# Ethernet_bridge_BOT.net
KiCad netlist of a schematic drawn in Altium Designer
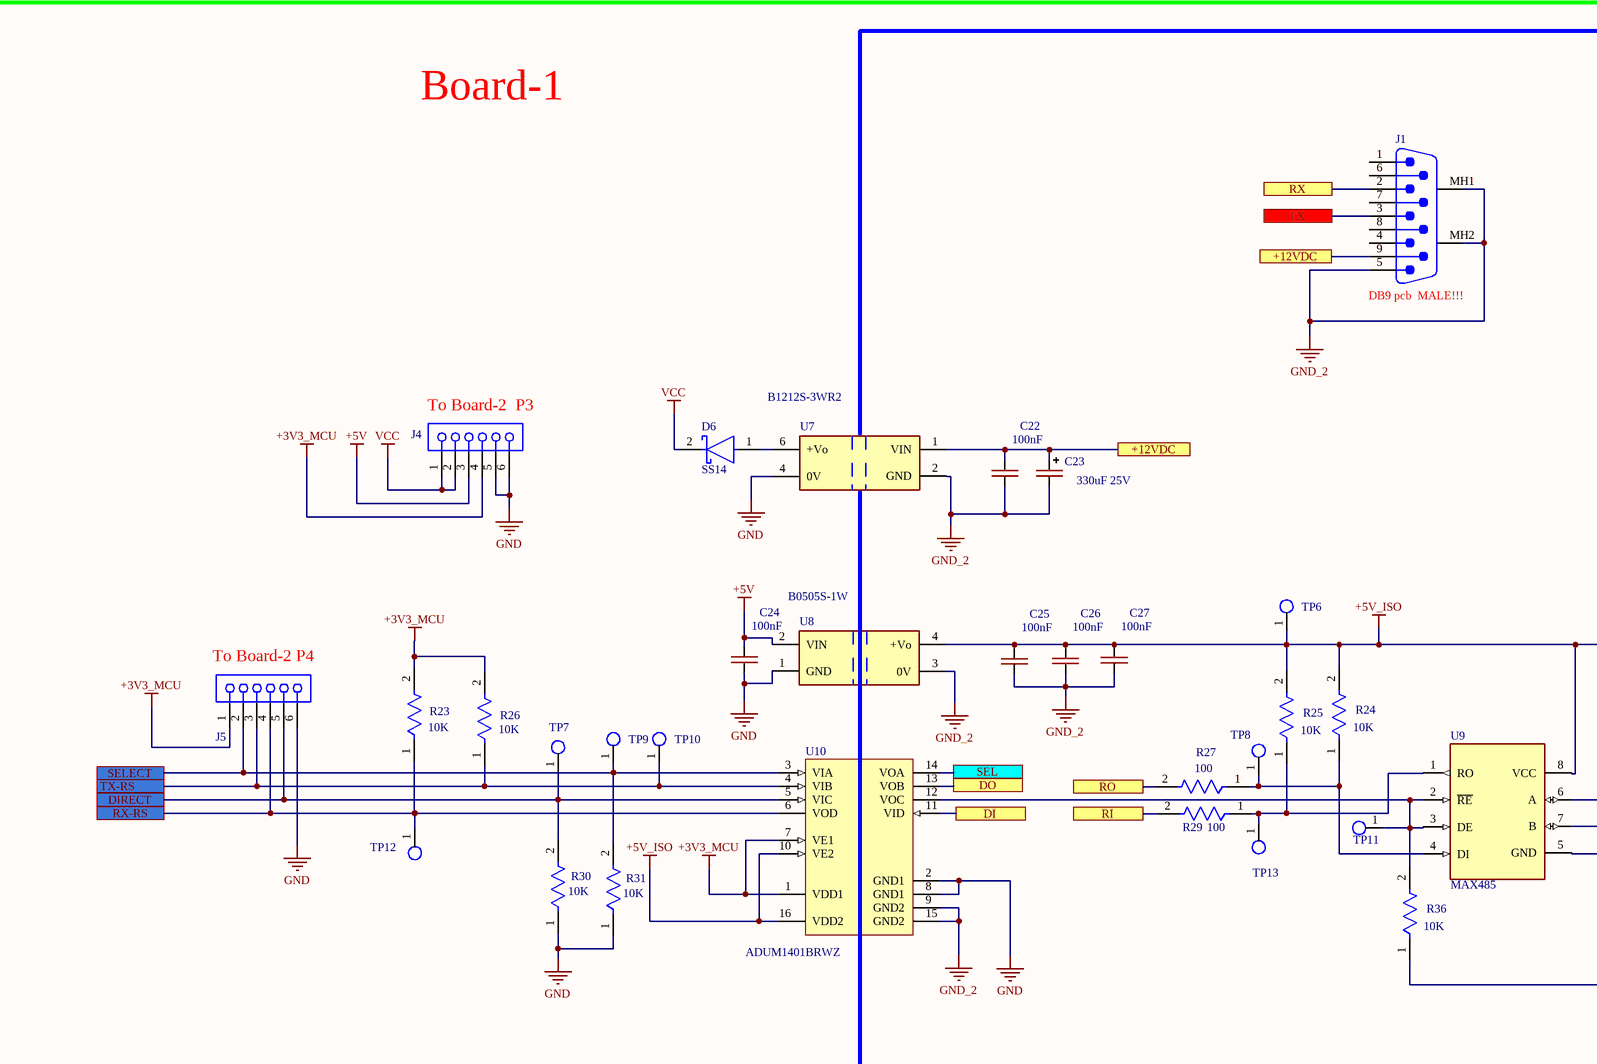
[diagram p0: Ethernet_bridge(BOT).SchDoc, left]
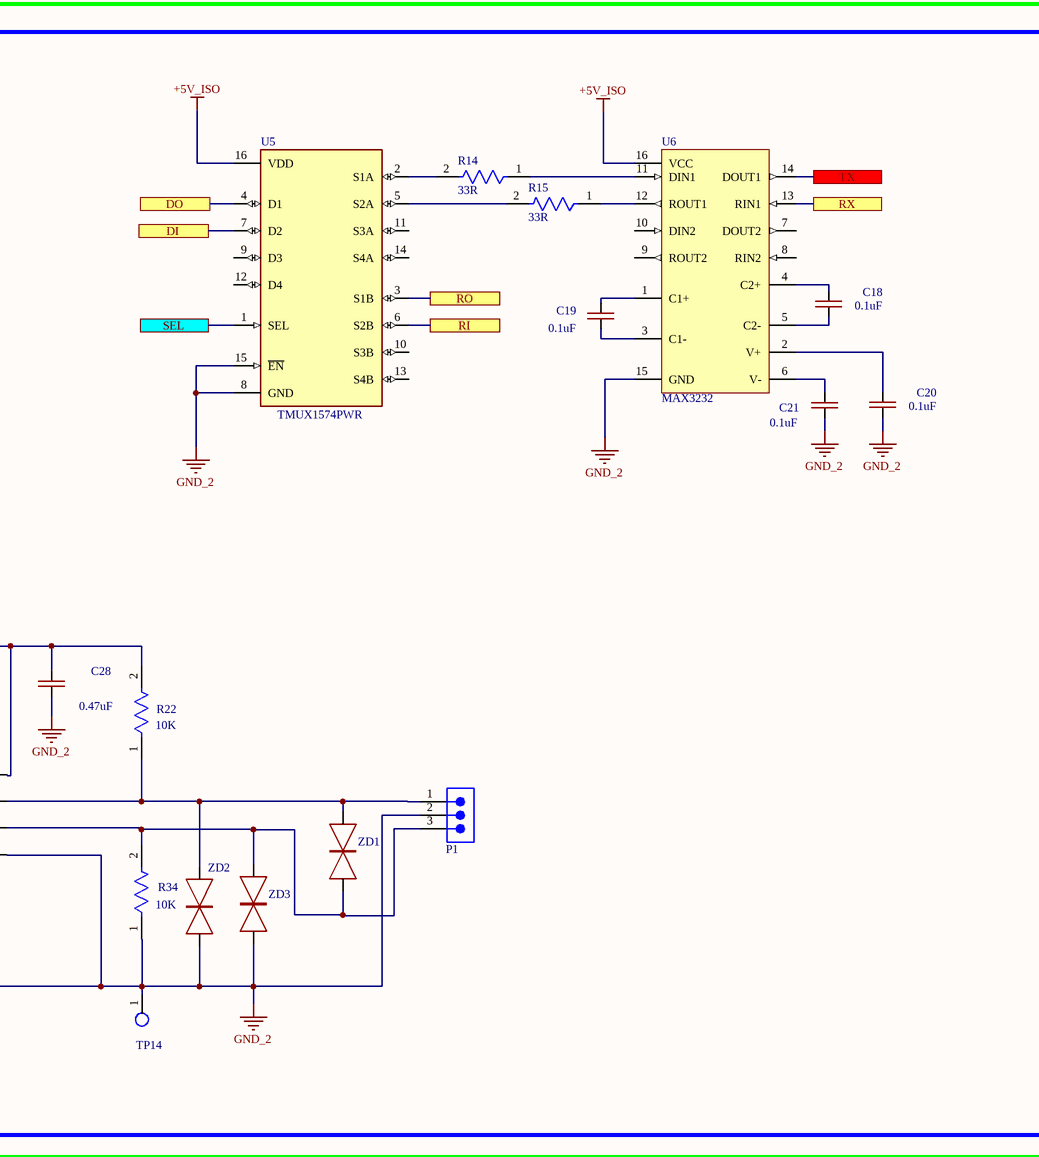
[diagram p1: Ethernet_bridge(BOT).SchDoc, right]

(export (version "E")
  (design (tool "Eeschema 10.0.6"))
  (components
    (comp (ref "C18")
      (value "0.1uF")
      (footprint "CAP-0603")
      (libsource (lib "PASSIVE_COMPONENTS") (part "CAP-NON-POLAR"))
    )
    (comp (ref "C19")
      (value "0.1uF")
      (footprint "CAP-0603")
      (libsource (lib "PASSIVE_COMPONENTS") (part "CAP-NON-POLAR"))
    )
    (comp (ref "C20")
      (value "0.1uF")
      (footprint "CAP-0603")
      (libsource (lib "PASSIVE_COMPONENTS") (part "CAP-NON-POLAR"))
    )
    (comp (ref "C21")
      (value "0.1uF")
      (footprint "CAP-0603")
      (libsource (lib "PASSIVE_COMPONENTS") (part "CAP-NON-POLAR"))
    )
    (comp (ref "C22")
      (value "100nF")
      (footprint "CAP-0603")
      (libsource (lib "PASSIVE_COMPONENTS") (part "CAP-NON-POLAR"))
    )
    (comp (ref "C23")
      (value "330uF 25V")
      (footprint "CAP_SMD_Size_E")
      (libsource (lib "PASSIVE_COMPONENTS") (part "CAP_POL_SMD"))
    )
    (comp (ref "C24")
      (value "100nF")
      (footprint "CAP-0603")
      (libsource (lib "PASSIVE_COMPONENTS") (part "CAP-NON-POLAR"))
    )
    (comp (ref "C25")
      (value "100nF")
      (footprint "CAP-0603")
      (libsource (lib "PASSIVE_COMPONENTS") (part "CAP-NON-POLAR"))
    )
    (comp (ref "C26")
      (value "100nF")
      (footprint "CAP-0603")
      (libsource (lib "PASSIVE_COMPONENTS") (part "CAP-NON-POLAR"))
    )
    (comp (ref "C27")
      (value "100nF")
      (footprint "CAP-0603")
      (libsource (lib "PASSIVE_COMPONENTS") (part "CAP-NON-POLAR"))
    )
    (comp (ref "C28")
      (value "0.47uF")
      (footprint "CAP-0805")
      (libsource (lib "PASSIVE_COMPONENTS") (part "CAP-NON-POLAR"))
    )
    (comp (ref "D6") (value "SS14") (footprint "DO-214-AC") (libsource (lib "Diodes") (part "SS14")))
    (comp (ref "J1")
      (value "DB9 pcb  MALE!!!")
      (footprint "DB-9_2")
      (libsource (lib "Connectors") (part "DB9"))
    )
    (comp (ref "J4")
      (value "61300611821")
      (footprint "61300611821")
      (description "WR-PHD Socket Header, THT, Vertical, pitch 2.54mm, 1 Row, 6P")
      (fields (field (name "MANUFACTURER") "Wurth Elektronik"))
      (libsource (lib "Altium_WR-PHD (rev22b)") (part "61300611821"))
    )
    (comp (ref "J5")
      (value "61300611821")
      (footprint "61300611821")
      (description "WR-PHD Socket Header, THT, Vertical, pitch 2.54mm, 1 Row, 6P")
      (fields (field (name "MANUFACTURER") "Wurth Elektronik"))
      (libsource (lib "Altium_WR-PHD (rev22b)") (part "61300611821"))
    )
    (comp (ref "P1")
      (value "691305340003")
      (footprint "691305340003")
      (description "WR-TBL Series 3053 Horizontal PCB Header, THT, pitch 3.81mm, 3p")
      (fields (field (name "MANUFACTURER") "Wurth Elektronik"))
      (libsource (lib "Altium_WR-TBL (rev23f)") (part "691305340003"))
    )
    (comp (ref "R14")
      (value "33R")
      (footprint "RES-0603")
      (libsource (lib "PASSIVE_COMPONENTS") (part "RES-CONST"))
    )
    (comp (ref "R15")
      (value "33R")
      (footprint "RES-0603")
      (libsource (lib "PASSIVE_COMPONENTS") (part "RES-CONST"))
    )
    (comp (ref "R22")
      (value "10K")
      (footprint "RES-0603")
      (libsource (lib "PASSIVE_COMPONENTS") (part "RES-CONST"))
    )
    (comp (ref "R23")
      (value "10K")
      (footprint "RES-0603")
      (libsource (lib "PASSIVE_COMPONENTS") (part "RES-CONST"))
    )
    (comp (ref "R24")
      (value "10K")
      (footprint "RES-0603")
      (libsource (lib "PASSIVE_COMPONENTS") (part "RES-CONST"))
    )
    (comp (ref "R25")
      (value "10K")
      (footprint "RES-0603")
      (libsource (lib "PASSIVE_COMPONENTS") (part "RES-CONST"))
    )
    (comp (ref "R26")
      (value "10K")
      (footprint "RES-0603")
      (libsource (lib "PASSIVE_COMPONENTS") (part "RES-CONST"))
    )
    (comp (ref "R27")
      (value "100")
      (footprint "RES-0603")
      (libsource (lib "PASSIVE_COMPONENTS") (part "RES-CONST"))
    )
    (comp (ref "R29")
      (value "100")
      (footprint "RES-0603")
      (libsource (lib "PASSIVE_COMPONENTS") (part "RES-CONST"))
    )
    (comp (ref "R30")
      (value "10K")
      (footprint "RES-0603")
      (libsource (lib "PASSIVE_COMPONENTS") (part "RES-CONST"))
    )
    (comp (ref "R31")
      (value "10K")
      (footprint "RES-0603")
      (libsource (lib "PASSIVE_COMPONENTS") (part "RES-CONST"))
    )
    (comp (ref "R34")
      (value "10K")
      (footprint "RES-0603")
      (libsource (lib "PASSIVE_COMPONENTS") (part "RES-CONST"))
    )
    (comp (ref "R36")
      (value "10K")
      (footprint "RES-0603")
      (libsource (lib "PASSIVE_COMPONENTS") (part "RES-CONST"))
    )
    (comp (ref "TP6")
      (value "Test_Point_PCB")
      (footprint "Test_Point")
      (description "Test_Point")
      (libsource (lib "Test_Point") (part "TP_PCB?"))
    )
    (comp (ref "TP7")
      (value "Test_Point_PCB")
      (footprint "Test_Point")
      (description "Test_Point")
      (libsource (lib "Test_Point") (part "TP_PCB?"))
    )
    (comp (ref "TP8")
      (value "Test_Point_PCB")
      (footprint "Test_Point")
      (description "Test_Point")
      (libsource (lib "Test_Point") (part "TP_PCB?"))
    )
    (comp (ref "TP9")
      (value "Test_Point_PCB")
      (footprint "Test_Point")
      (description "Test_Point")
      (libsource (lib "Test_Point") (part "TP_PCB?"))
    )
    (comp (ref "TP10")
      (value "Test_Point_PCB")
      (footprint "Test_Point")
      (description "Test_Point")
      (libsource (lib "Test_Point") (part "TP_PCB?"))
    )
    (comp (ref "TP11")
      (value "Test_Point_PCB")
      (footprint "Test_Point")
      (description "Test_Point")
      (libsource (lib "Test_Point") (part "TP_PCB?"))
    )
    (comp (ref "TP12")
      (value "Test_Point_PCB")
      (footprint "Test_Point")
      (description "Test_Point")
      (libsource (lib "Test_Point") (part "TP_PCB?"))
    )
    (comp (ref "TP13")
      (value "~")
      (footprint "Test_Point")
      (description "Test_Point")
      (libsource (lib "Connectors") (part "TP_PCB?"))
    )
    (comp (ref "TP14")
      (value "Test_Point_PCB")
      (footprint "Test_Point")
      (description "Test_Point")
      (libsource (lib "Test_Point") (part "TP_PCB?"))
    )
    (comp (ref "U5")
      (value "TMUX1574PWR")
      (footprint "TSSOP-16-A")
      (libsource (lib "Integrated_Circuts") (part "TMUX1574PWR"))
    )
    (comp (ref "U6")
      (value "MAX3232")
      (footprint "SOIC-16-M")
      (libsource (lib "Integrated_Circuts") (part "MAX3232"))
    )
    (comp (ref "U7")
      (value "B1212S-3WR2")
      (footprint "B1212S-3WR2")
      (libsource (lib "Integrated_Circuts") (part "B1212S-3WR2"))
    )
    (comp (ref "U8")
      (value "B0505S-1W")
      (footprint "B0505S-1W")
      (libsource (lib "Integrated_Circuts") (part "B0505S-1W"))
    )
    (comp (ref "U9")
      (value "MAX485")
      (footprint "SOIC-8-MFG")
      (libsource (lib "Integrated_Circuts") (part "MAX485"))
    )
    (comp (ref "U10")
      (value "ADUM1401BRWZ")
      (footprint "ADI-RW-16_M")
      (fields (field (name "MANUFACTURER") "Analog Devices"))
      (libsource (lib "Altium Content Vault") (part "ADI-ADUMX4X1-16"))
    )
    (comp (ref "ZD1")
      (value "P6SMB16CA")
      (footprint "DO-214AA")
      (libsource (lib "P6SMB16CA") (part "P6SMB16CA"))
    )
    (comp (ref "ZD2")
      (value "P6SMB16CA")
      (footprint "DO-214AA")
      (libsource (lib "P6SMB16CA") (part "P6SMB16CA"))
    )
    (comp (ref "ZD3")
      (value "P6SMB16CA")
      (footprint "DO-214AA")
      (libsource (lib "P6SMB16CA") (part "P6SMB16CA"))
    )
  )
  (nets
    (net (code "1") (name "+3V3_MCU") (class "Default")
      (node (ref "J4") (pin "4") (pinfunction "4_4") (pintype "passive"))
      (node (ref "J5") (pin "1") (pinfunction "1_1") (pintype "passive"))
      (node (ref "R23") (pin "2") (pinfunction "2_2") (pintype "passive"))
      (node (ref "R26") (pin "2") (pinfunction "2_2") (pintype "passive"))
      (node (ref "U10") (pin "1") (pinfunction "VDD1_1") (pintype "power_in"))
      (node (ref "U10") (pin "7") (pinfunction "VE1_7") (pintype "input"))
    )
    (net (code "2") (name "+5V") (class "Default")
      (node (ref "C24") (pin "2") (pinfunction "2_2") (pintype "passive"))
      (node (ref "J4") (pin "3") (pinfunction "3_3") (pintype "passive"))
      (node (ref "U8") (pin "2") (pinfunction "VIN_2") (pintype "power_in"))
    )
    (net (code "3") (name "+5V_ISO") (class "Default")
      (node (ref "C25") (pin "2") (pinfunction "2_2") (pintype "passive"))
      (node (ref "C26") (pin "2") (pinfunction "2_2") (pintype "passive"))
      (node (ref "C27") (pin "2") (pinfunction "2_2") (pintype "passive"))
      (node (ref "C28") (pin "1") (pinfunction "1_1") (pintype "passive"))
      (node (ref "R22") (pin "2") (pinfunction "2_2") (pintype "passive"))
      (node (ref "R24") (pin "2") (pinfunction "2_2") (pintype "passive"))
      (node (ref "R25") (pin "2") (pinfunction "2_2") (pintype "passive"))
      (node (ref "TP6") (pin "1") (pinfunction "G9_1") (pintype "passive"))
      (node (ref "U10") (pin "10") (pinfunction "VE2_10") (pintype "input"))
      (node (ref "U10") (pin "16") (pinfunction "VDD2_16") (pintype "power_in"))
      (node (ref "U5") (pin "16") (pinfunction "VDD_16") (pintype "power_in"))
      (node (ref "U6") (pin "16") (pinfunction "VCC_16") (pintype "power_in"))
      (node (ref "U8") (pin "4") (pinfunction "+Vo_4") (pintype "power_in"))
      (node (ref "U9") (pin "8") (pinfunction "VCC_8") (pintype "power_in"))
    )
    (net (code "4") (name "/+12VDC") (class "Default")
      (node (ref "C22") (pin "2") (pinfunction "2_2") (pintype "passive"))
      (node (ref "C23") (pin "1") (pinfunction "+_1") (pintype "passive"))
      (node (ref "J1") (pin "9") (pinfunction "9_9") (pintype "passive"))
      (node (ref "U7") (pin "1") (pinfunction "VIN_1") (pintype "power_in"))
    )
    (net (code "5") (name "/DI") (class "Default")
      (node (ref "U10") (pin "11") (pinfunction "VID_11") (pintype "input"))
      (node (ref "U5") (pin "7") (pinfunction "D2_7") (pintype "bidirectional"))
    )
    (net (code "6") (name "/DIRECT") (class "Default")
      (node (ref "J5") (pin "5") (pinfunction "5_5") (pintype "passive"))
      (node (ref "R30") (pin "2") (pinfunction "2_2") (pintype "passive"))
      (node (ref "TP7") (pin "1") (pinfunction "G9_1") (pintype "passive"))
      (node (ref "U10") (pin "5") (pinfunction "VIC_5") (pintype "input"))
    )
    (net (code "7") (name "/DO") (class "Default")
      (node (ref "U10") (pin "13") (pinfunction "VOB_13") (pintype "tri_state"))
      (node (ref "U5") (pin "4") (pinfunction "D1_4") (pintype "bidirectional"))
    )
    (net (code "8") (name "/RI") (class "Default")
      (node (ref "R29") (pin "2") (pinfunction "2_2") (pintype "passive"))
      (node (ref "U5") (pin "6") (pinfunction "S2B_6") (pintype "bidirectional"))
    )
    (net (code "9") (name "/RO") (class "Default")
      (node (ref "R27") (pin "2") (pinfunction "2_2") (pintype "passive"))
      (node (ref "U5") (pin "3") (pinfunction "S1B_3") (pintype "bidirectional"))
    )
    (net (code "10") (name "/RX") (class "Default")
      (node (ref "J1") (pin "2") (pinfunction "2_2") (pintype "passive"))
      (node (ref "U6") (pin "13") (pinfunction "RIN1_13") (pintype "input"))
    )
    (net (code "11") (name "/RX-RS") (class "Default")
      (node (ref "J5") (pin "4") (pinfunction "4_4") (pintype "passive"))
      (node (ref "R23") (pin "1") (pinfunction "1_1") (pintype "passive"))
      (node (ref "TP12") (pin "1") (pinfunction "G9_1") (pintype "passive"))
      (node (ref "U10") (pin "6") (pinfunction "VOD_6") (pintype "tri_state"))
    )
    (net (code "12") (name "/SEL") (class "Default")
      (node (ref "U10") (pin "14") (pinfunction "VOA_14") (pintype "tri_state"))
      (node (ref "U5") (pin "1") (pinfunction "SEL_1") (pintype "input"))
    )
    (net (code "13") (name "/SELECT") (class "Default")
      (node (ref "J5") (pin "2") (pinfunction "2_2") (pintype "passive"))
      (node (ref "R31") (pin "2") (pinfunction "2_2") (pintype "passive"))
      (node (ref "TP9") (pin "1") (pinfunction "G9_1") (pintype "passive"))
      (node (ref "U10") (pin "3") (pinfunction "VIA_3") (pintype "input"))
    )
    (net (code "14") (name "/TX") (class "Default")
      (node (ref "J1") (pin "3") (pinfunction "3_3") (pintype "passive"))
      (node (ref "U6") (pin "14") (pinfunction "DOUT1_14") (pintype "output"))
    )
    (net (code "15") (name "/TX-RS") (class "Default")
      (node (ref "J5") (pin "3") (pinfunction "3_3") (pintype "passive"))
      (node (ref "R26") (pin "1") (pinfunction "1_1") (pintype "passive"))
      (node (ref "TP10") (pin "1") (pinfunction "G9_1") (pintype "passive"))
      (node (ref "U10") (pin "4") (pinfunction "VIB_4") (pintype "input"))
    )
    (net (code "16") (name "GND") (class "Default")
      (node (ref "C24") (pin "1") (pinfunction "1_1") (pintype "passive"))
      (node (ref "J4") (pin "5") (pinfunction "5_5") (pintype "passive"))
      (node (ref "J4") (pin "6") (pinfunction "6_6") (pintype "passive"))
      (node (ref "J5") (pin "6") (pinfunction "6_6") (pintype "passive"))
      (node (ref "R30") (pin "1") (pinfunction "1_1") (pintype "passive"))
      (node (ref "R31") (pin "1") (pinfunction "1_1") (pintype "passive"))
      (node (ref "U10") (pin "2") (pinfunction "GND1_2") (pintype "power_in"))
      (node (ref "U10") (pin "8") (pinfunction "GND1_8") (pintype "power_in"))
      (node (ref "U7") (pin "4") (pinfunction "0V_4") (pintype "power_in"))
      (node (ref "U8") (pin "1") (pinfunction "GND_1") (pintype "power_in"))
    )
    (net (code "17") (name "GND_2") (class "Default")
      (node (ref "C20") (pin "1") (pinfunction "1_1") (pintype "passive"))
      (node (ref "C21") (pin "1") (pinfunction "1_1") (pintype "passive"))
      (node (ref "C22") (pin "1") (pinfunction "1_1") (pintype "passive"))
      (node (ref "C23") (pin "2") (pinfunction "-_2") (pintype "passive"))
      (node (ref "C25") (pin "1") (pinfunction "1_1") (pintype "passive"))
      (node (ref "C26") (pin "1") (pinfunction "1_1") (pintype "passive"))
      (node (ref "C27") (pin "1") (pinfunction "1_1") (pintype "passive"))
      (node (ref "C28") (pin "2") (pinfunction "2_2") (pintype "passive"))
      (node (ref "J1") (pin "5") (pinfunction "5_5") (pintype "passive"))
      (node (ref "J1") (pin "MH1") (pinfunction "MH1_MH1") (pintype "passive"))
      (node (ref "J1") (pin "MH2") (pinfunction "MH2_MH2") (pintype "passive"))
      (node (ref "P1") (pin "2") (pinfunction "2_2") (pintype "passive"))
      (node (ref "R34") (pin "1") (pinfunction "1_1") (pintype "passive"))
      (node (ref "R36") (pin "1") (pinfunction "1_1") (pintype "passive"))
      (node (ref "TP14") (pin "1") (pinfunction "G9_1") (pintype "passive"))
      (node (ref "U10") (pin "15") (pinfunction "GND2_15") (pintype "power_in"))
      (node (ref "U10") (pin "9") (pinfunction "GND2_9") (pintype "power_in"))
      (node (ref "U5") (pin "15") (pinfunction "~{EN}_15") (pintype "input"))
      (node (ref "U5") (pin "8") (pinfunction "GND_8") (pintype "power_in"))
      (node (ref "U6") (pin "15") (pinfunction "GND_15") (pintype "power_in"))
      (node (ref "U7") (pin "2") (pinfunction "GND_2") (pintype "power_in"))
      (node (ref "U8") (pin "3") (pinfunction "0V_3") (pintype "power_in"))
      (node (ref "U9") (pin "5") (pinfunction "GND_5") (pintype "power_in"))
      (node (ref "ZD2") (pin "1") (pinfunction "A_1") (pintype "passive"))
      (node (ref "ZD3") (pin "1") (pinfunction "A_1") (pintype "passive"))
    )
    (net (code "18") (name "Net-(D6-A)") (class "Default")
      (node (ref "D6") (pin "1") (pinfunction "A_1") (pintype "passive"))
      (node (ref "U7") (pin "6") (pinfunction "+Vo_6") (pintype "power_in"))
    )
    (net (code "19") (name "Net-(TP8-G9)") (class "Default")
      (node (ref "R24") (pin "1") (pinfunction "1_1") (pintype "passive"))
      (node (ref "R27") (pin "1") (pinfunction "1_1") (pintype "passive"))
      (node (ref "TP8") (pin "1") (pinfunction "G9_1") (pintype "passive"))
      (node (ref "U9") (pin "4") (pinfunction "DI_4") (pintype "input"))
    )
    (net (code "20") (name "Net-(TP11-G9)") (class "Default")
      (node (ref "R36") (pin "2") (pinfunction "2_2") (pintype "passive"))
      (node (ref "TP11") (pin "1") (pinfunction "G9_1") (pintype "passive"))
      (node (ref "U10") (pin "12") (pinfunction "VOC_12") (pintype "tri_state"))
      (node (ref "U9") (pin "2") (pinfunction "~{RE}_2") (pintype "input"))
      (node (ref "U9") (pin "3") (pinfunction "DE_3") (pintype "input"))
    )
    (net (code "21") (name "Net-(TP13-G9)") (class "Default")
      (node (ref "R25") (pin "1") (pinfunction "1_1") (pintype "passive"))
      (node (ref "R29") (pin "1") (pinfunction "1_1") (pintype "passive"))
      (node (ref "TP13") (pin "1") (pinfunction "G9_1") (pintype "passive"))
      (node (ref "U9") (pin "1") (pinfunction "RO_1") (pintype "output"))
    )
    (net (code "22") (name "Net-(U5-S1A)") (class "Default")
      (node (ref "R14") (pin "2") (pinfunction "2_2") (pintype "passive"))
      (node (ref "U5") (pin "2") (pinfunction "S1A_2") (pintype "bidirectional"))
    )
    (net (code "23") (name "Net-(U5-S2A)") (class "Default")
      (node (ref "R15") (pin "2") (pinfunction "2_2") (pintype "passive"))
      (node (ref "U5") (pin "5") (pinfunction "S2A_5") (pintype "bidirectional"))
    )
    (net (code "24") (name "Net-(U6-C1+)") (class "Default")
      (node (ref "C19") (pin "2") (pinfunction "2_2") (pintype "passive"))
      (node (ref "U6") (pin "1") (pinfunction "C1+_1") (pintype "passive"))
    )
    (net (code "25") (name "Net-(U6-C1-)") (class "Default")
      (node (ref "C19") (pin "1") (pinfunction "1_1") (pintype "passive"))
      (node (ref "U6") (pin "3") (pinfunction "C1-_3") (pintype "passive"))
    )
    (net (code "26") (name "Net-(U6-C2+)") (class "Default")
      (node (ref "C18") (pin "2") (pinfunction "2_2") (pintype "passive"))
      (node (ref "U6") (pin "4") (pinfunction "C2+_4") (pintype "passive"))
    )
    (net (code "27") (name "Net-(U6-C2-)") (class "Default")
      (node (ref "C18") (pin "1") (pinfunction "1_1") (pintype "passive"))
      (node (ref "U6") (pin "5") (pinfunction "C2-_5") (pintype "passive"))
    )
    (net (code "28") (name "Net-(U6-DIN1)") (class "Default")
      (node (ref "R14") (pin "1") (pinfunction "1_1") (pintype "passive"))
      (node (ref "U6") (pin "11") (pinfunction "DIN1_11") (pintype "input"))
    )
    (net (code "29") (name "Net-(U6-ROUT1)") (class "Default")
      (node (ref "R15") (pin "1") (pinfunction "1_1") (pintype "passive"))
      (node (ref "U6") (pin "12") (pinfunction "ROUT1_12") (pintype "output"))
    )
    (net (code "30") (name "Net-(U6-V+)") (class "Default")
      (node (ref "C20") (pin "2") (pinfunction "2_2") (pintype "passive"))
      (node (ref "U6") (pin "2") (pinfunction "V+_2") (pintype "power_in"))
    )
    (net (code "31") (name "Net-(U6-V-)") (class "Default")
      (node (ref "C21") (pin "2") (pinfunction "2_2") (pintype "passive"))
      (node (ref "U6") (pin "6") (pinfunction "V-_6") (pintype "power_in"))
    )
    (net (code "32") (name "Net-(U9-A)") (class "Default")
      (node (ref "P1") (pin "1") (pinfunction "1_1") (pintype "passive"))
      (node (ref "R22") (pin "1") (pinfunction "1_1") (pintype "passive"))
      (node (ref "U9") (pin "6") (pinfunction "A_6") (pintype "bidirectional"))
      (node (ref "ZD1") (pin "2") (pinfunction "A_2") (pintype "passive"))
      (node (ref "ZD2") (pin "2") (pinfunction "A_2") (pintype "passive"))
    )
    (net (code "33") (name "Net-(U9-B)") (class "Default")
      (node (ref "P1") (pin "3") (pinfunction "3_3") (pintype "passive"))
      (node (ref "R34") (pin "2") (pinfunction "2_2") (pintype "passive"))
      (node (ref "U9") (pin "7") (pinfunction "B_7") (pintype "bidirectional"))
      (node (ref "ZD1") (pin "1") (pinfunction "A_1") (pintype "passive"))
      (node (ref "ZD3") (pin "2") (pinfunction "A_2") (pintype "passive"))
    )
    (net (code "34") (name "VCC") (class "Default")
      (node (ref "D6") (pin "2") (pinfunction "C_2") (pintype "passive"))
      (node (ref "J4") (pin "1") (pinfunction "1_1") (pintype "passive"))
      (node (ref "J4") (pin "2") (pinfunction "2_2") (pintype "passive"))
    )
    (net (code "35") (name "unconnected-(J1-Pad1)") (class "Default")
      (node (ref "J1") (pin "1") (pinfunction "1_1") (pintype "passive"))
    )
    (net (code "36") (name "unconnected-(J1-Pad4)") (class "Default")
      (node (ref "J1") (pin "4") (pinfunction "4_4") (pintype "passive"))
    )
    (net (code "37") (name "unconnected-(J1-Pad6)") (class "Default")
      (node (ref "J1") (pin "6") (pinfunction "6_6") (pintype "passive"))
    )
    (net (code "38") (name "unconnected-(J1-Pad7)") (class "Default")
      (node (ref "J1") (pin "7") (pinfunction "7_7") (pintype "passive"))
    )
    (net (code "39") (name "unconnected-(J1-Pad8)") (class "Default")
      (node (ref "J1") (pin "8") (pinfunction "8_8") (pintype "passive"))
    )
    (net (code "40") (name "unconnected-(U5-D3-Pad9)") (class "Default")
      (node (ref "U5") (pin "9") (pinfunction "D3_9") (pintype "bidirectional"))
    )
    (net (code "41") (name "unconnected-(U5-D4-Pad12)") (class "Default")
      (node (ref "U5") (pin "12") (pinfunction "D4_12") (pintype "bidirectional"))
    )
    (net (code "42") (name "unconnected-(U5-S3A-Pad11)") (class "Default")
      (node (ref "U5") (pin "11") (pinfunction "S3A_11") (pintype "bidirectional"))
    )
    (net (code "43") (name "unconnected-(U5-S3B-Pad10)") (class "Default")
      (node (ref "U5") (pin "10") (pinfunction "S3B_10") (pintype "bidirectional"))
    )
    (net (code "44") (name "unconnected-(U5-S4A-Pad14)") (class "Default")
      (node (ref "U5") (pin "14") (pinfunction "S4A_14") (pintype "bidirectional"))
    )
    (net (code "45") (name "unconnected-(U5-S4B-Pad13)") (class "Default")
      (node (ref "U5") (pin "13") (pinfunction "S4B_13") (pintype "bidirectional"))
    )
    (net (code "46") (name "unconnected-(U6-DIN2-Pad10)") (class "Default")
      (node (ref "U6") (pin "10") (pinfunction "DIN2_10") (pintype "input"))
    )
    (net (code "47") (name "unconnected-(U6-DOUT2-Pad7)") (class "Default")
      (node (ref "U6") (pin "7") (pinfunction "DOUT2_7") (pintype "output"))
    )
    (net (code "48") (name "unconnected-(U6-RIN2-Pad8)") (class "Default")
      (node (ref "U6") (pin "8") (pinfunction "RIN2_8") (pintype "input"))
    )
    (net (code "49") (name "unconnected-(U6-ROUT2-Pad9)") (class "Default")
      (node (ref "U6") (pin "9") (pinfunction "ROUT2_9") (pintype "output"))
    )
  )
)
